# adc_dac_conn.net
KiCad netlist of a schematic drawn in Altium Designer
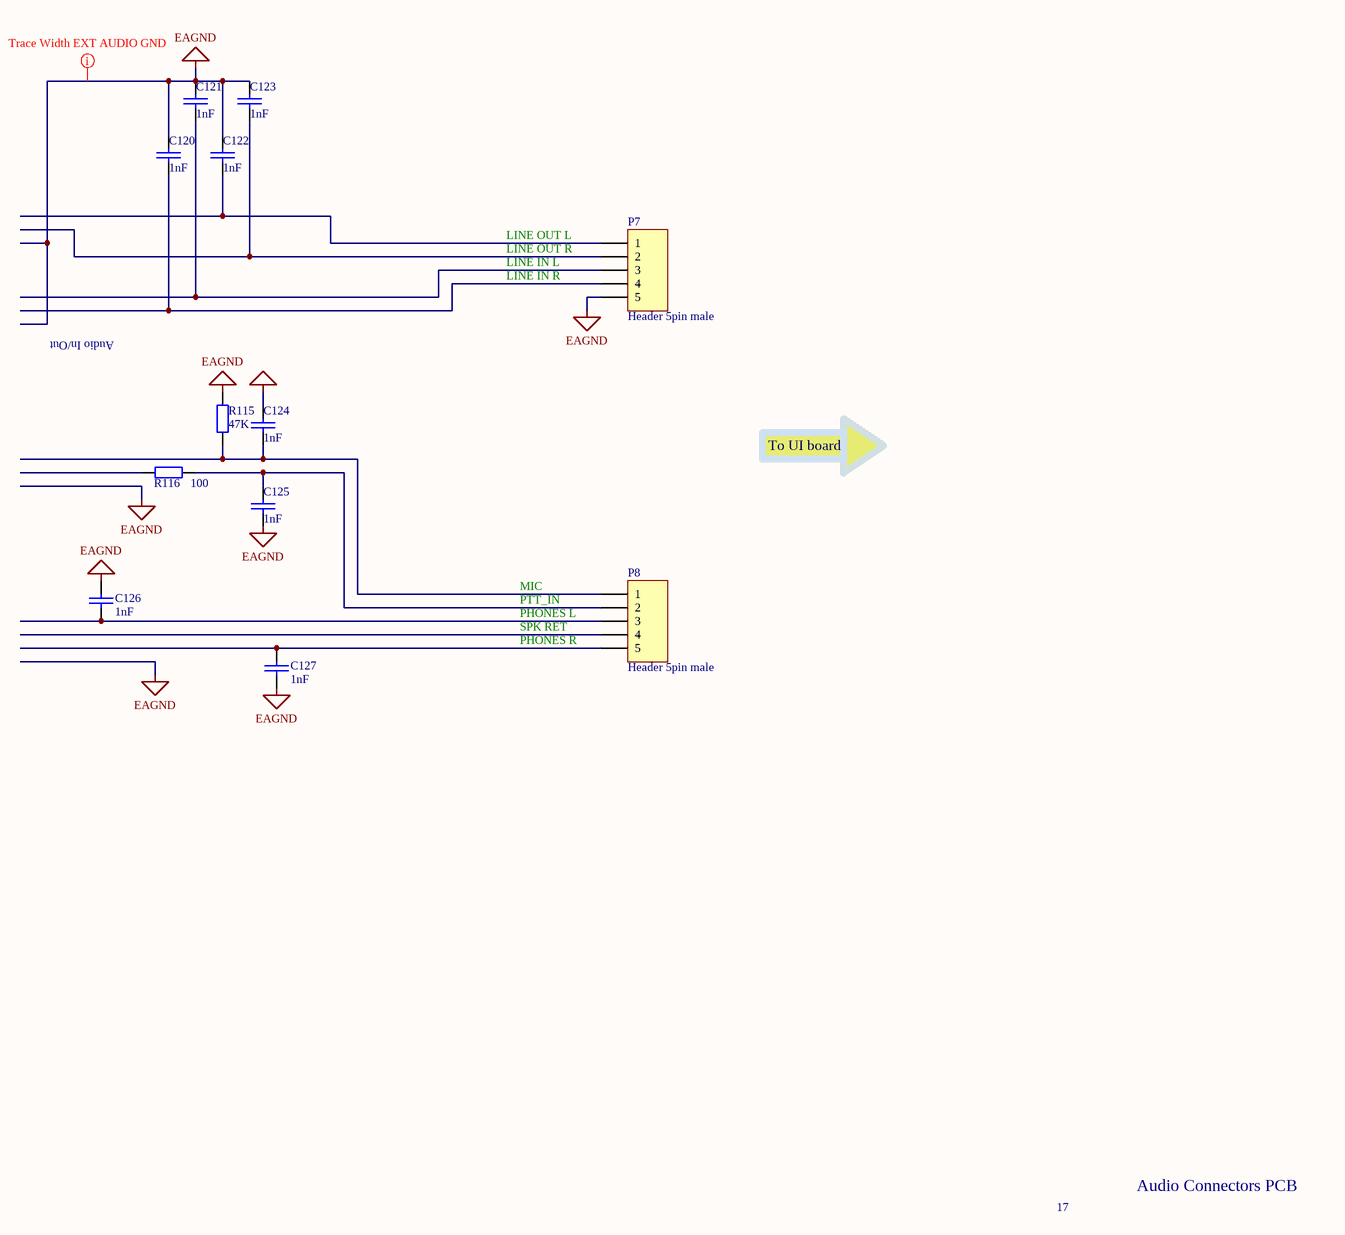
[diagram p0: adc_dac_conn.SchDoc]

(export (version "E")
  (design (tool "Eeschema 10.0.6"))
  (components
    (comp (ref "C120")
      (value "1nF")
      (footprint "0805")
      (description "Capacitor")
      (libsource (lib "mcHF_ui") (part "CAP"))
    )
    (comp (ref "C121")
      (value "1nF")
      (footprint "0805")
      (description "Capacitor")
      (libsource (lib "mcHF_ui") (part "CAP"))
    )
    (comp (ref "C122")
      (value "1nF")
      (footprint "0805")
      (description "Capacitor")
      (libsource (lib "mcHF_ui") (part "CAP"))
    )
    (comp (ref "C123")
      (value "1nF")
      (footprint "0805")
      (description "Capacitor")
      (libsource (lib "mcHF_ui") (part "CAP"))
    )
    (comp (ref "C124")
      (value "1nF")
      (footprint "0805")
      (description "Capacitor")
      (libsource (lib "mcHF_ui") (part "CAP"))
    )
    (comp (ref "C125")
      (value "1nF")
      (footprint "0805")
      (description "Capacitor")
      (libsource (lib "mcHF_ui") (part "CAP"))
    )
    (comp (ref "C126")
      (value "1nF")
      (footprint "0805")
      (description "Capacitor")
      (libsource (lib "mcHF_ui") (part "CAP"))
    )
    (comp (ref "C127")
      (value "1nF")
      (footprint "0805")
      (description "Capacitor")
      (libsource (lib "mcHF_ui") (part "CAP"))
    )
    (comp (ref "P7")
      (value "Header 5pin male")
      (footprint "HDR1X5")
      (description "Header, 5-Pin")
      (libsource (lib "__ui") (part "Header 5"))
    )
    (comp (ref "P8")
      (value "Header 5pin male")
      (footprint "HDR1X5")
      (description "Header, 5-Pin")
      (libsource (lib "__ui") (part "Header 5"))
    )
    (comp (ref "R115")
      (value "47K")
      (footprint "0805")
      (description "Resistor")
      (libsource (lib "") (part "RES_1"))
    )
    (comp (ref "R116")
      (value "100")
      (footprint "0805")
      (description "Resistor")
      (libsource (lib "mcHF_ui") (part "RES"))
    )
  )
  (nets
    (net (code "1") (name "EAGND") (class "Default")
      (node (ref "C120") (pin "1") (pinfunction "1_1") (pintype "passive"))
      (node (ref "C121") (pin "1") (pinfunction "1_1") (pintype "passive"))
      (node (ref "C122") (pin "1") (pinfunction "1_1") (pintype "passive"))
      (node (ref "C123") (pin "1") (pinfunction "1_1") (pintype "passive"))
      (node (ref "C124") (pin "1") (pinfunction "1_1") (pintype "passive"))
      (node (ref "C125") (pin "2") (pinfunction "2_2") (pintype "passive"))
      (node (ref "C126") (pin "2") (pinfunction "2_2") (pintype "passive"))
      (node (ref "C127") (pin "1") (pinfunction "1_1") (pintype "passive"))
      (node (ref "P7") (pin "5") (pinfunction "5_5") (pintype "passive"))
      (node (ref "R115") (pin "2") (pinfunction "2_2") (pintype "passive"))
    )
    (net (code "2") (name "Net-(C120-Pad2)") (class "Default")
      (node (ref "C120") (pin "2") (pinfunction "2_2") (pintype "passive"))
      (node (ref "P7") (pin "4") (pinfunction "4_4") (pintype "passive"))
    )
    (net (code "3") (name "Net-(C121-Pad2)") (class "Default")
      (node (ref "C121") (pin "2") (pinfunction "2_2") (pintype "passive"))
      (node (ref "P7") (pin "3") (pinfunction "3_3") (pintype "passive"))
    )
    (net (code "4") (name "Net-(C122-Pad2)") (class "Default")
      (node (ref "C122") (pin "2") (pinfunction "2_2") (pintype "passive"))
      (node (ref "P7") (pin "1") (pinfunction "1_1") (pintype "passive"))
    )
    (net (code "5") (name "Net-(C123-Pad2)") (class "Default")
      (node (ref "C123") (pin "2") (pinfunction "2_2") (pintype "passive"))
      (node (ref "P7") (pin "2") (pinfunction "2_2") (pintype "passive"))
    )
    (net (code "6") (name "Net-(C124-Pad2)") (class "Default")
      (node (ref "C124") (pin "2") (pinfunction "2_2") (pintype "passive"))
      (node (ref "P8") (pin "1") (pinfunction "1_1") (pintype "passive"))
      (node (ref "R115") (pin "1") (pinfunction "1_1") (pintype "passive"))
    )
    (net (code "7") (name "Net-(C125-Pad1)") (class "Default")
      (node (ref "C125") (pin "1") (pinfunction "1_1") (pintype "passive"))
      (node (ref "P8") (pin "2") (pinfunction "2_2") (pintype "passive"))
      (node (ref "R116") (pin "2") (pinfunction "2_2") (pintype "passive"))
    )
    (net (code "8") (name "Net-(C126-Pad1)") (class "Default")
      (node (ref "C126") (pin "1") (pinfunction "1_1") (pintype "passive"))
      (node (ref "P8") (pin "3") (pinfunction "3_3") (pintype "passive"))
    )
    (net (code "9") (name "Net-(C127-Pad2)") (class "Default")
      (node (ref "C127") (pin "2") (pinfunction "2_2") (pintype "passive"))
      (node (ref "P8") (pin "5") (pinfunction "5_5") (pintype "passive"))
    )
    (net (code "10") (name "unconnected-(P8-Pad4)") (class "Default")
      (node (ref "P8") (pin "4") (pinfunction "4_4") (pintype "passive"))
    )
    (net (code "11") (name "unconnected-(R116-Pad1)") (class "Default")
      (node (ref "R116") (pin "1") (pinfunction "1_1") (pintype "passive"))
    )
  )
)
